# CanTransceiver.net
KiCad netlist of a schematic drawn in Altium Designer
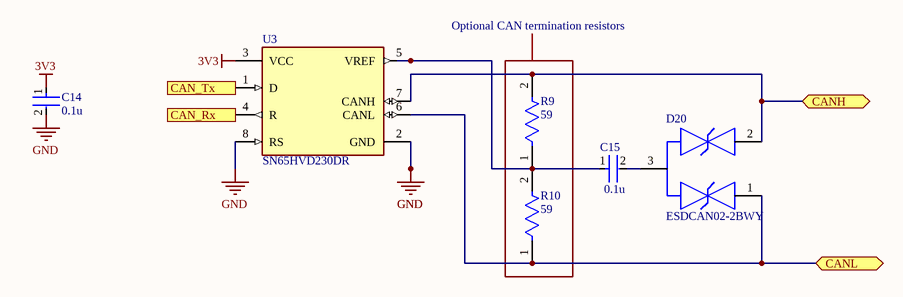
[diagram p0: CanTransceiver.SchDoc]

(export (version "E")
  (design (tool "Eeschema 10.0.6"))
  (components
    (comp (ref "C14")
      (value "0.1u")
      (footprint "FP-C0603C-CF-MFG")
      (description "CAP CER 0.1UF 50V X7R 0603")
      (fields (field (name "TOLERANCE") "0.1") (field (name "MANUFACTURER") "KEMET"))
      (libsource (lib "Altium Content Vault") (part "b4654b650e69147ec39a6b967a45e02"))
    )
    (comp (ref "C15")
      (value "0.1u")
      (footprint "FP-C0603C-CF-MFG")
      (description "CAP CER 0.1UF 50V X7R 0603")
      (fields (field (name "TOLERANCE") "0.1") (field (name "MANUFACTURER") "KEMET"))
      (libsource (lib "Altium Content Vault") (part "b4654b650e69147ec39a6b967a45e02"))
    )
    (comp (ref "D20")
      (value "ESDCAN02-2BWY")
      (footprint "FP-SOT323-3L-MFG")
      (description "TVS DIODE 26.5V 44V SOT323-3")
      (fields
        (field (name "MANUFACTURER") "STMicroelectronics")
        (field (name "OCTOPART") "https://octopart.com/esdcan02-2bwy-stmicroelectronics-58631133")
      )
      (libsource (lib "Altium Content Vault") (part "0b9019fb5e52ed66df21ec1535be59d"))
    )
    (comp (ref "R9")
      (value "59")
      (footprint "FP-CRCW0805-e3-IPC_B")
      (description "RES Thick Film, 59Ω, 1%, 0.125W, 100ppm/°C, 0805")
      (fields (field (name "TOLERANCE") "1%"))
      (libsource (lib "Altium Content Vault") (part "1029c3af85768c4190bb7ad29bc67b5"))
    )
    (comp (ref "R10")
      (value "59")
      (footprint "FP-CRCW0805-e3-IPC_B")
      (description "RES Thick Film, 59Ω, 1%, 0.125W, 100ppm/°C, 0805")
      (fields (field (name "TOLERANCE") "1%"))
      (libsource (lib "Altium Content Vault") (part "1029c3af85768c4190bb7ad29bc67b5"))
    )
    (comp (ref "U3")
      (value "SN65HVD230DR")
      (footprint "FP-D0008A-IPC_A")
      (description "IC TRANSCEIVER HALF 1/1 8SOIC")
      (libsource (lib "Altium Content Vault") (part "43b56812b1adf0e60a7acfb7c27ab91"))
    )
  )
  (nets
    (net (code "1") (name "/CANH") (class "Default")
      (node (ref "D20") (pin "2") (pinfunction "2_2") (pintype "passive"))
      (node (ref "R9") (pin "2") (pinfunction "2_2") (pintype "passive"))
      (node (ref "U3") (pin "7") (pinfunction "CANH_7") (pintype "bidirectional"))
    )
    (net (code "2") (name "/CANL") (class "Default")
      (node (ref "D20") (pin "1") (pinfunction "1_1") (pintype "passive"))
      (node (ref "R10") (pin "1") (pinfunction "1_1") (pintype "passive"))
      (node (ref "U3") (pin "6") (pinfunction "CANL_6") (pintype "bidirectional"))
    )
    (net (code "3") (name "/CAN_Rx") (class "Default")
      (node (ref "U3") (pin "4") (pinfunction "R_4") (pintype "output"))
    )
    (net (code "4") (name "/CAN_Tx") (class "Default")
      (node (ref "U3") (pin "1") (pinfunction "D_1") (pintype "input"))
    )
    (net (code "5") (name "3V3") (class "Default")
      (node (ref "C14") (pin "1") (pinfunction "1_1") (pintype "passive"))
      (node (ref "U3") (pin "3") (pinfunction "VCC_3") (pintype "power_in"))
    )
    (net (code "6") (name "GND") (class "Default")
      (node (ref "C14") (pin "2") (pinfunction "2_2") (pintype "passive"))
      (node (ref "U3") (pin "2") (pinfunction "GND_2") (pintype "power_in"))
      (node (ref "U3") (pin "8") (pinfunction "RS_8") (pintype "input"))
    )
    (net (code "7") (name "Net-(C15-Pad2)") (class "Default")
      (node (ref "C15") (pin "2") (pinfunction "2_2") (pintype "passive"))
      (node (ref "D20") (pin "3") (pinfunction "3_3") (pintype "passive"))
    )
    (net (code "8") (name "Net-(U3-VREF)") (class "Default")
      (node (ref "C15") (pin "1") (pinfunction "1_1") (pintype "passive"))
      (node (ref "R10") (pin "2") (pinfunction "2_2") (pintype "passive"))
      (node (ref "R9") (pin "1") (pinfunction "1_1") (pintype "passive"))
      (node (ref "U3") (pin "5") (pinfunction "VREF_5") (pintype "output"))
    )
  )
)
